# Power_supply.net
KiCad netlist of a schematic drawn in Altium Designer
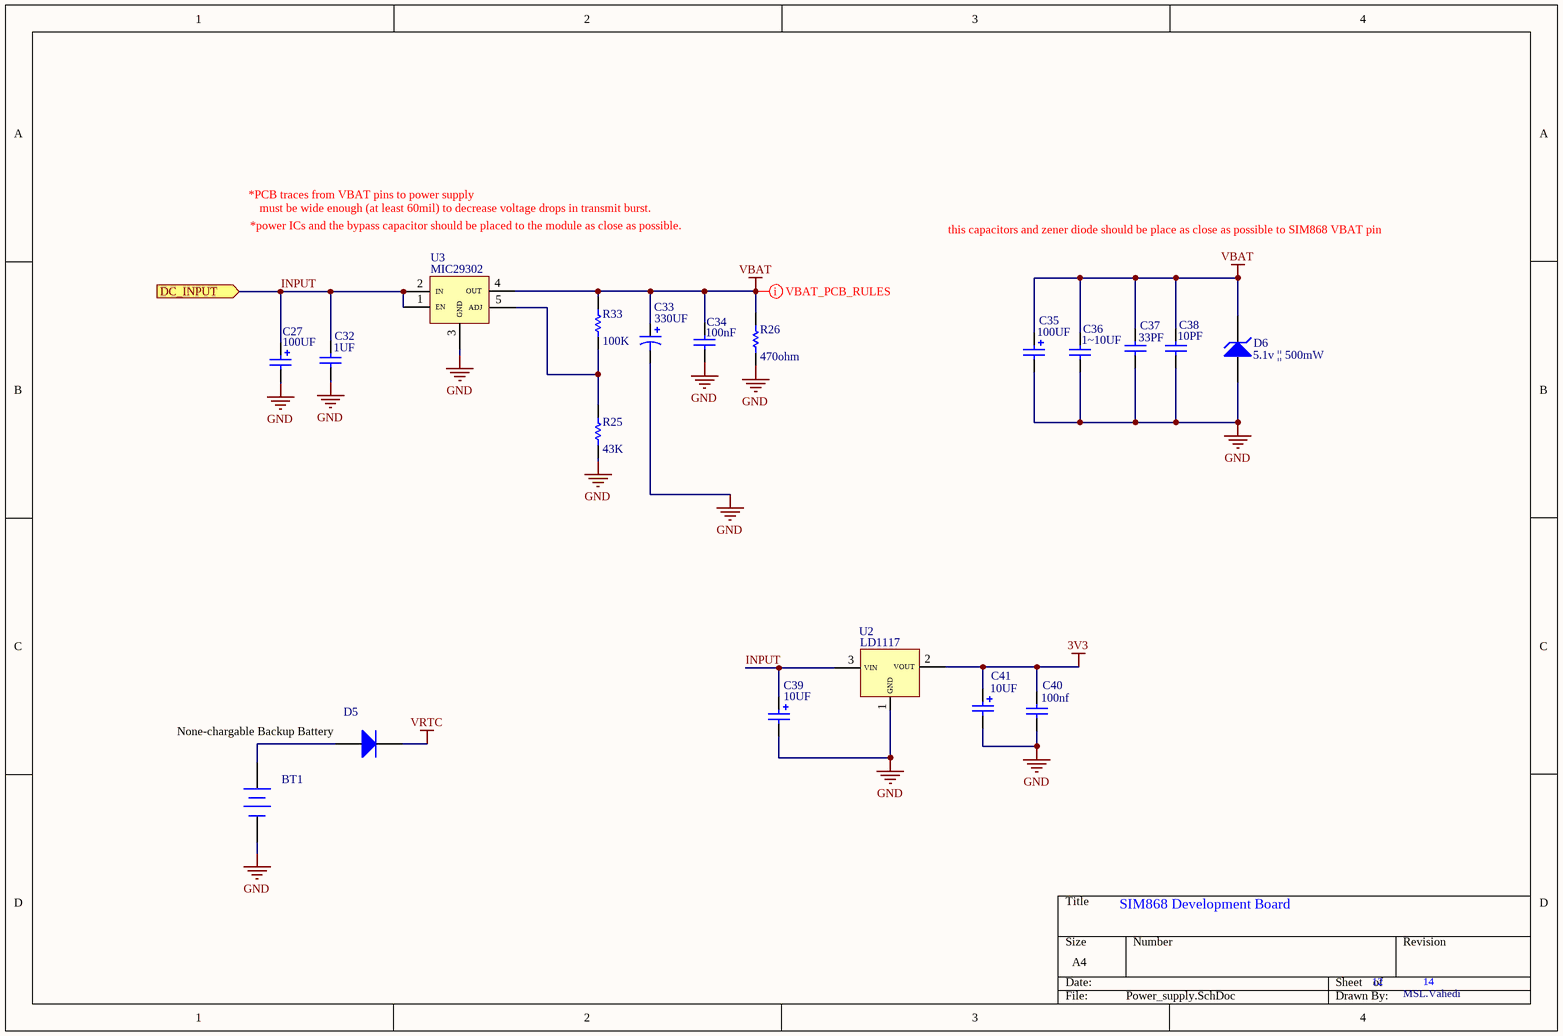
[diagram p0: Power_supply.SchDoc]

(export (version "E")
  (design (tool "Eeschema 10.0.6"))
  (components
    (comp (ref "BT1")
      (value "None-chargable Backup Battery")
      (footprint "HDR1X2")
      (description "Multicell Battery")
      (fields (field (name "PUBLISHER") "Altium Limited"))
      (libsource (lib "Miscellaneous Devices") (part "Battery"))
    )
    (comp (ref "C27")
      (value "100UF")
      (footprint "KEMET_A")
      (description "Polarized Capacitor (Axial)")
      (fields (field (name "PUBLISHER") "Altium Limited"))
      (libsource (lib "Miscellaneous Devices") (part "Cap Pol2"))
    )
    (comp (ref "C32")
      (value "1UF")
      (footprint "CAP0805")
      (description "Capacitor")
      (fields (field (name "PUBLISHER") "Altium Limited"))
      (libsource (lib "Miscellaneous Devices") (part "Cap"))
    )
    (comp (ref "C33")
      (value "330UF")
      (footprint "KEMET_A")
      (description "Polarized Capacitor (Radial)")
      (fields (field (name "PUBLISHER") "Altium Limited"))
      (libsource (lib "Miscellaneous Devices") (part "Cap Pol1"))
    )
    (comp (ref "C34")
      (value "100nF")
      (footprint "CAP0805")
      (description "Capacitor")
      (fields (field (name "PUBLISHER") "Altium Limited"))
      (libsource (lib "Miscellaneous Devices") (part "Cap"))
    )
    (comp (ref "C35")
      (value "100UF")
      (footprint "CAP0805")
      (description "Polarized Capacitor (Axial)")
      (fields (field (name "PUBLISHER") "Altium Limited"))
      (libsource (lib "Miscellaneous Devices") (part "Cap Pol2"))
    )
    (comp (ref "C36")
      (value "1~10UF")
      (footprint "CAP0805")
      (description "Capacitor")
      (fields (field (name "PUBLISHER") "Altium Limited"))
      (libsource (lib "Miscellaneous Devices") (part "Cap"))
    )
    (comp (ref "C37")
      (value "33PF")
      (footprint "CAP0805")
      (description "Capacitor")
      (fields (field (name "PUBLISHER") "Altium Limited"))
      (libsource (lib "Miscellaneous Devices") (part "Cap"))
    )
    (comp (ref "C38")
      (value "10PF")
      (footprint "CAP0805")
      (description "Capacitor")
      (fields (field (name "PUBLISHER") "Altium Limited"))
      (libsource (lib "Miscellaneous Devices") (part "Cap"))
    )
    (comp (ref "C39")
      (value "10UF")
      (footprint "KEMET_A")
      (description "Polarized Capacitor (Axial)")
      (fields (field (name "PUBLISHER") "Altium Limited"))
      (libsource (lib "Miscellaneous Devices") (part "Cap Pol2"))
    )
    (comp (ref "C40")
      (value "100nf")
      (footprint "CAP0805")
      (description "Capacitor")
      (fields (field (name "PUBLISHER") "Altium Limited"))
      (libsource (lib "Miscellaneous Devices") (part "Cap"))
    )
    (comp (ref "C41")
      (value "10UF")
      (footprint "KEMET_A")
      (description "Polarized Capacitor (Axial)")
      (fields (field (name "PUBLISHER") "Altium Limited"))
      (libsource (lib "Miscellaneous Devices") (part "Cap Pol2"))
    )
    (comp (ref "D5")
      (value "~")
      (footprint "SOD-123")
      (description "1 Amp General Purpose Rectifier")
      (fields (field (name "PUBLISHER") "Altium Limited"))
      (libsource (lib "Miscellaneous Devices") (part "Diode 1N4007"))
    )
    (comp (ref "D6")
      (value "5.1v Ζ 500mW")
      (footprint "SOD-123")
      (description "MMSZ5231BT1G Ζ PZ3DV2H Ζ MMSZ4689-V Ζ CDZ55V1SM")
      (fields (field (name "PUBLISHER") "Altium Limited"))
      (libsource (lib "Miscellaneous Devices") (part "D Zener"))
    )
    (comp (ref "R25")
      (value "43K")
      (footprint "RES0805")
      (description "Resistor")
      (fields (field (name "PUBLISHER") "Altium Limited"))
      (libsource (lib "Miscellaneous Devices") (part "Res1"))
    )
    (comp (ref "R26")
      (value "470ohm")
      (footprint "RES0805")
      (description "Resistor")
      (fields (field (name "PUBLISHER") "Altium Limited"))
      (libsource (lib "Miscellaneous Devices") (part "Res1"))
    )
    (comp (ref "R33")
      (value "100K")
      (footprint "RES0805")
      (description "Resistor")
      (fields (field (name "PUBLISHER") "Altium Limited"))
      (libsource (lib "Miscellaneous Devices") (part "Res1"))
    )
    (comp (ref "U2")
      (value "LD1117")
      (footprint "*DPAK228P972X240-3N")
      (libsource (lib "LD117DT33") (part "LD1117"))
    )
    (comp (ref "U3")
      (value "MIC29302")
      (footprint "MIC29302")
      (description "3A Fast-Response LDO Regulator")
      (libsource (lib "Schlib1") (part "MIC29302"))
    )
  )
  (nets
    (net (code "1") (name "/INPUT") (class "Default")
      (node (ref "C27") (pin "1") (pinfunction "1_1") (pintype "passive"))
      (node (ref "C32") (pin "2") (pinfunction "2_2") (pintype "passive"))
      (node (ref "C39") (pin "1") (pinfunction "1_1") (pintype "passive"))
      (node (ref "U2") (pin "3") (pinfunction "VIN_3") (pintype "passive"))
      (node (ref "U3") (pin "1") (pinfunction "EN_1") (pintype "passive"))
      (node (ref "U3") (pin "2") (pinfunction "IN_2") (pintype "passive"))
    )
    (net (code "2") (name "3V3") (class "Default")
      (node (ref "C40") (pin "2") (pinfunction "2_2") (pintype "passive"))
      (node (ref "C41") (pin "1") (pinfunction "1_1") (pintype "passive"))
      (node (ref "U2") (pin "2") (pinfunction "VOUT_2") (pintype "passive"))
    )
    (net (code "3") (name "GND") (class "Default")
      (node (ref "BT1") (pin "2") (pinfunction "-_2") (pintype "passive"))
      (node (ref "C27") (pin "2") (pinfunction "2_2") (pintype "passive"))
      (node (ref "C32") (pin "1") (pinfunction "1_1") (pintype "passive"))
      (node (ref "C33") (pin "2") (pinfunction "2_2") (pintype "passive"))
      (node (ref "C34") (pin "1") (pinfunction "1_1") (pintype "passive"))
      (node (ref "C35") (pin "2") (pinfunction "2_2") (pintype "passive"))
      (node (ref "C36") (pin "2") (pinfunction "2_2") (pintype "passive"))
      (node (ref "C37") (pin "2") (pinfunction "2_2") (pintype "passive"))
      (node (ref "C38") (pin "2") (pinfunction "2_2") (pintype "passive"))
      (node (ref "C39") (pin "2") (pinfunction "2_2") (pintype "passive"))
      (node (ref "C40") (pin "1") (pinfunction "1_1") (pintype "passive"))
      (node (ref "C41") (pin "2") (pinfunction "2_2") (pintype "passive"))
      (node (ref "D6") (pin "1") (pinfunction "A_1") (pintype "passive"))
      (node (ref "R25") (pin "1") (pinfunction "1_1") (pintype "passive"))
      (node (ref "R26") (pin "1") (pinfunction "1_1") (pintype "passive"))
      (node (ref "U2") (pin "1") (pinfunction "GND_1") (pintype "passive"))
      (node (ref "U3") (pin "3") (pinfunction "GND_3") (pintype "passive"))
    )
    (net (code "4") (name "Net-(BT1-+)") (class "Default")
      (node (ref "BT1") (pin "1") (pinfunction "+_1") (pintype "passive"))
      (node (ref "D5") (pin "1") (pinfunction "A_1") (pintype "passive"))
    )
    (net (code "5") (name "Net-(U3-ADJ)") (class "Default")
      (node (ref "R25") (pin "2") (pinfunction "2_2") (pintype "passive"))
      (node (ref "R33") (pin "1") (pinfunction "1_1") (pintype "passive"))
      (node (ref "U3") (pin "5") (pinfunction "ADJ_5") (pintype "passive"))
    )
    (net (code "6") (name "VBAT") (class "Default")
      (node (ref "C33") (pin "1") (pinfunction "1_1") (pintype "passive"))
      (node (ref "C34") (pin "2") (pinfunction "2_2") (pintype "passive"))
      (node (ref "C35") (pin "1") (pinfunction "1_1") (pintype "passive"))
      (node (ref "C36") (pin "1") (pinfunction "1_1") (pintype "passive"))
      (node (ref "C37") (pin "1") (pinfunction "1_1") (pintype "passive"))
      (node (ref "C38") (pin "1") (pinfunction "1_1") (pintype "passive"))
      (node (ref "D6") (pin "2") (pinfunction "K_2") (pintype "passive"))
      (node (ref "R26") (pin "2") (pinfunction "2_2") (pintype "passive"))
      (node (ref "R33") (pin "2") (pinfunction "2_2") (pintype "passive"))
      (node (ref "U3") (pin "4") (pinfunction "OUT_4") (pintype "passive"))
    )
    (net (code "7") (name "VRTC") (class "Default")
      (node (ref "D5") (pin "2") (pinfunction "K_2") (pintype "passive"))
    )
  )
)
